# mocd208m.net
KiCad netlist of a schematic drawn in EAGLE
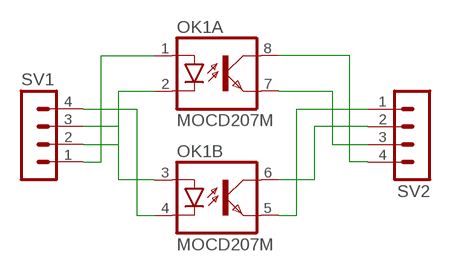
[diagram p0: schematic, sheet 1]

(export (version "E")
  (design (tool "Eeschema 10.0.6"))
  (components
    (comp (ref "OK1")
      (value "MOCD207M")
      (footprint "eagle-import:SOIC08-FAIRCHILD")
      (fields (field (name "MF") "FAIRCHILD SEMICONDUCTOR") (field (name "MPN") "MOCD207-M"))
      (libsource (lib "eagle-import") (part "MOCD20M7"))
    )
    (comp (ref "SV1")
      (value "MA04-1")
      (footprint "eagle-import:MA04-1")
      (libsource (lib "eagle-import") (part "MA04-1"))
    )
    (comp (ref "SV2")
      (value "MA04-1")
      (footprint "eagle-import:MA04-1")
      (libsource (lib "eagle-import") (part "MA04-1"))
    )
  )
  (nets
    (net (code "1") (name "Net-(OK1A-A)") (class "Default")
      (node (ref "OK1") (pin "1") (pinfunction "A_1") (pintype "passive"))
      (node (ref "SV1") (pin "1") (pinfunction "1_1") (pintype "passive"))
    )
    (net (code "2") (name "Net-(OK1A-C)") (class "Default")
      (node (ref "OK1") (pin "2") (pinfunction "C_2") (pintype "passive"))
      (node (ref "SV1") (pin "2") (pinfunction "2_2") (pintype "passive"))
    )
    (net (code "3") (name "Net-(OK1A-COL)") (class "Default")
      (node (ref "OK1") (pin "8") (pinfunction "COL_8") (pintype "passive"))
      (node (ref "SV2") (pin "4") (pinfunction "4_4") (pintype "passive"))
    )
    (net (code "4") (name "Net-(OK1A-EMIT)") (class "Default")
      (node (ref "OK1") (pin "7") (pinfunction "EMIT_7") (pintype "passive"))
      (node (ref "SV2") (pin "3") (pinfunction "3_3") (pintype "passive"))
    )
    (net (code "5") (name "Net-(OK1B-A)") (class "Default")
      (node (ref "OK1") (pin "3") (pinfunction "A_3") (pintype "passive"))
      (node (ref "SV1") (pin "3") (pinfunction "3_3") (pintype "passive"))
    )
    (net (code "6") (name "Net-(OK1B-C)") (class "Default")
      (node (ref "OK1") (pin "4") (pinfunction "C_4") (pintype "passive"))
      (node (ref "SV1") (pin "4") (pinfunction "4_4") (pintype "passive"))
    )
    (net (code "7") (name "Net-(OK1B-COL)") (class "Default")
      (node (ref "OK1") (pin "6") (pinfunction "COL_6") (pintype "passive"))
      (node (ref "SV2") (pin "2") (pinfunction "2_2") (pintype "passive"))
    )
    (net (code "8") (name "Net-(OK1B-EMIT)") (class "Default")
      (node (ref "OK1") (pin "5") (pinfunction "EMIT_5") (pintype "passive"))
      (node (ref "SV2") (pin "1") (pinfunction "1_1") (pintype "passive"))
    )
  )
)
